# 51-2001-01-15_04_Power_Module_Schematic.net
KiCad netlist of a schematic drawn in Altium Designer
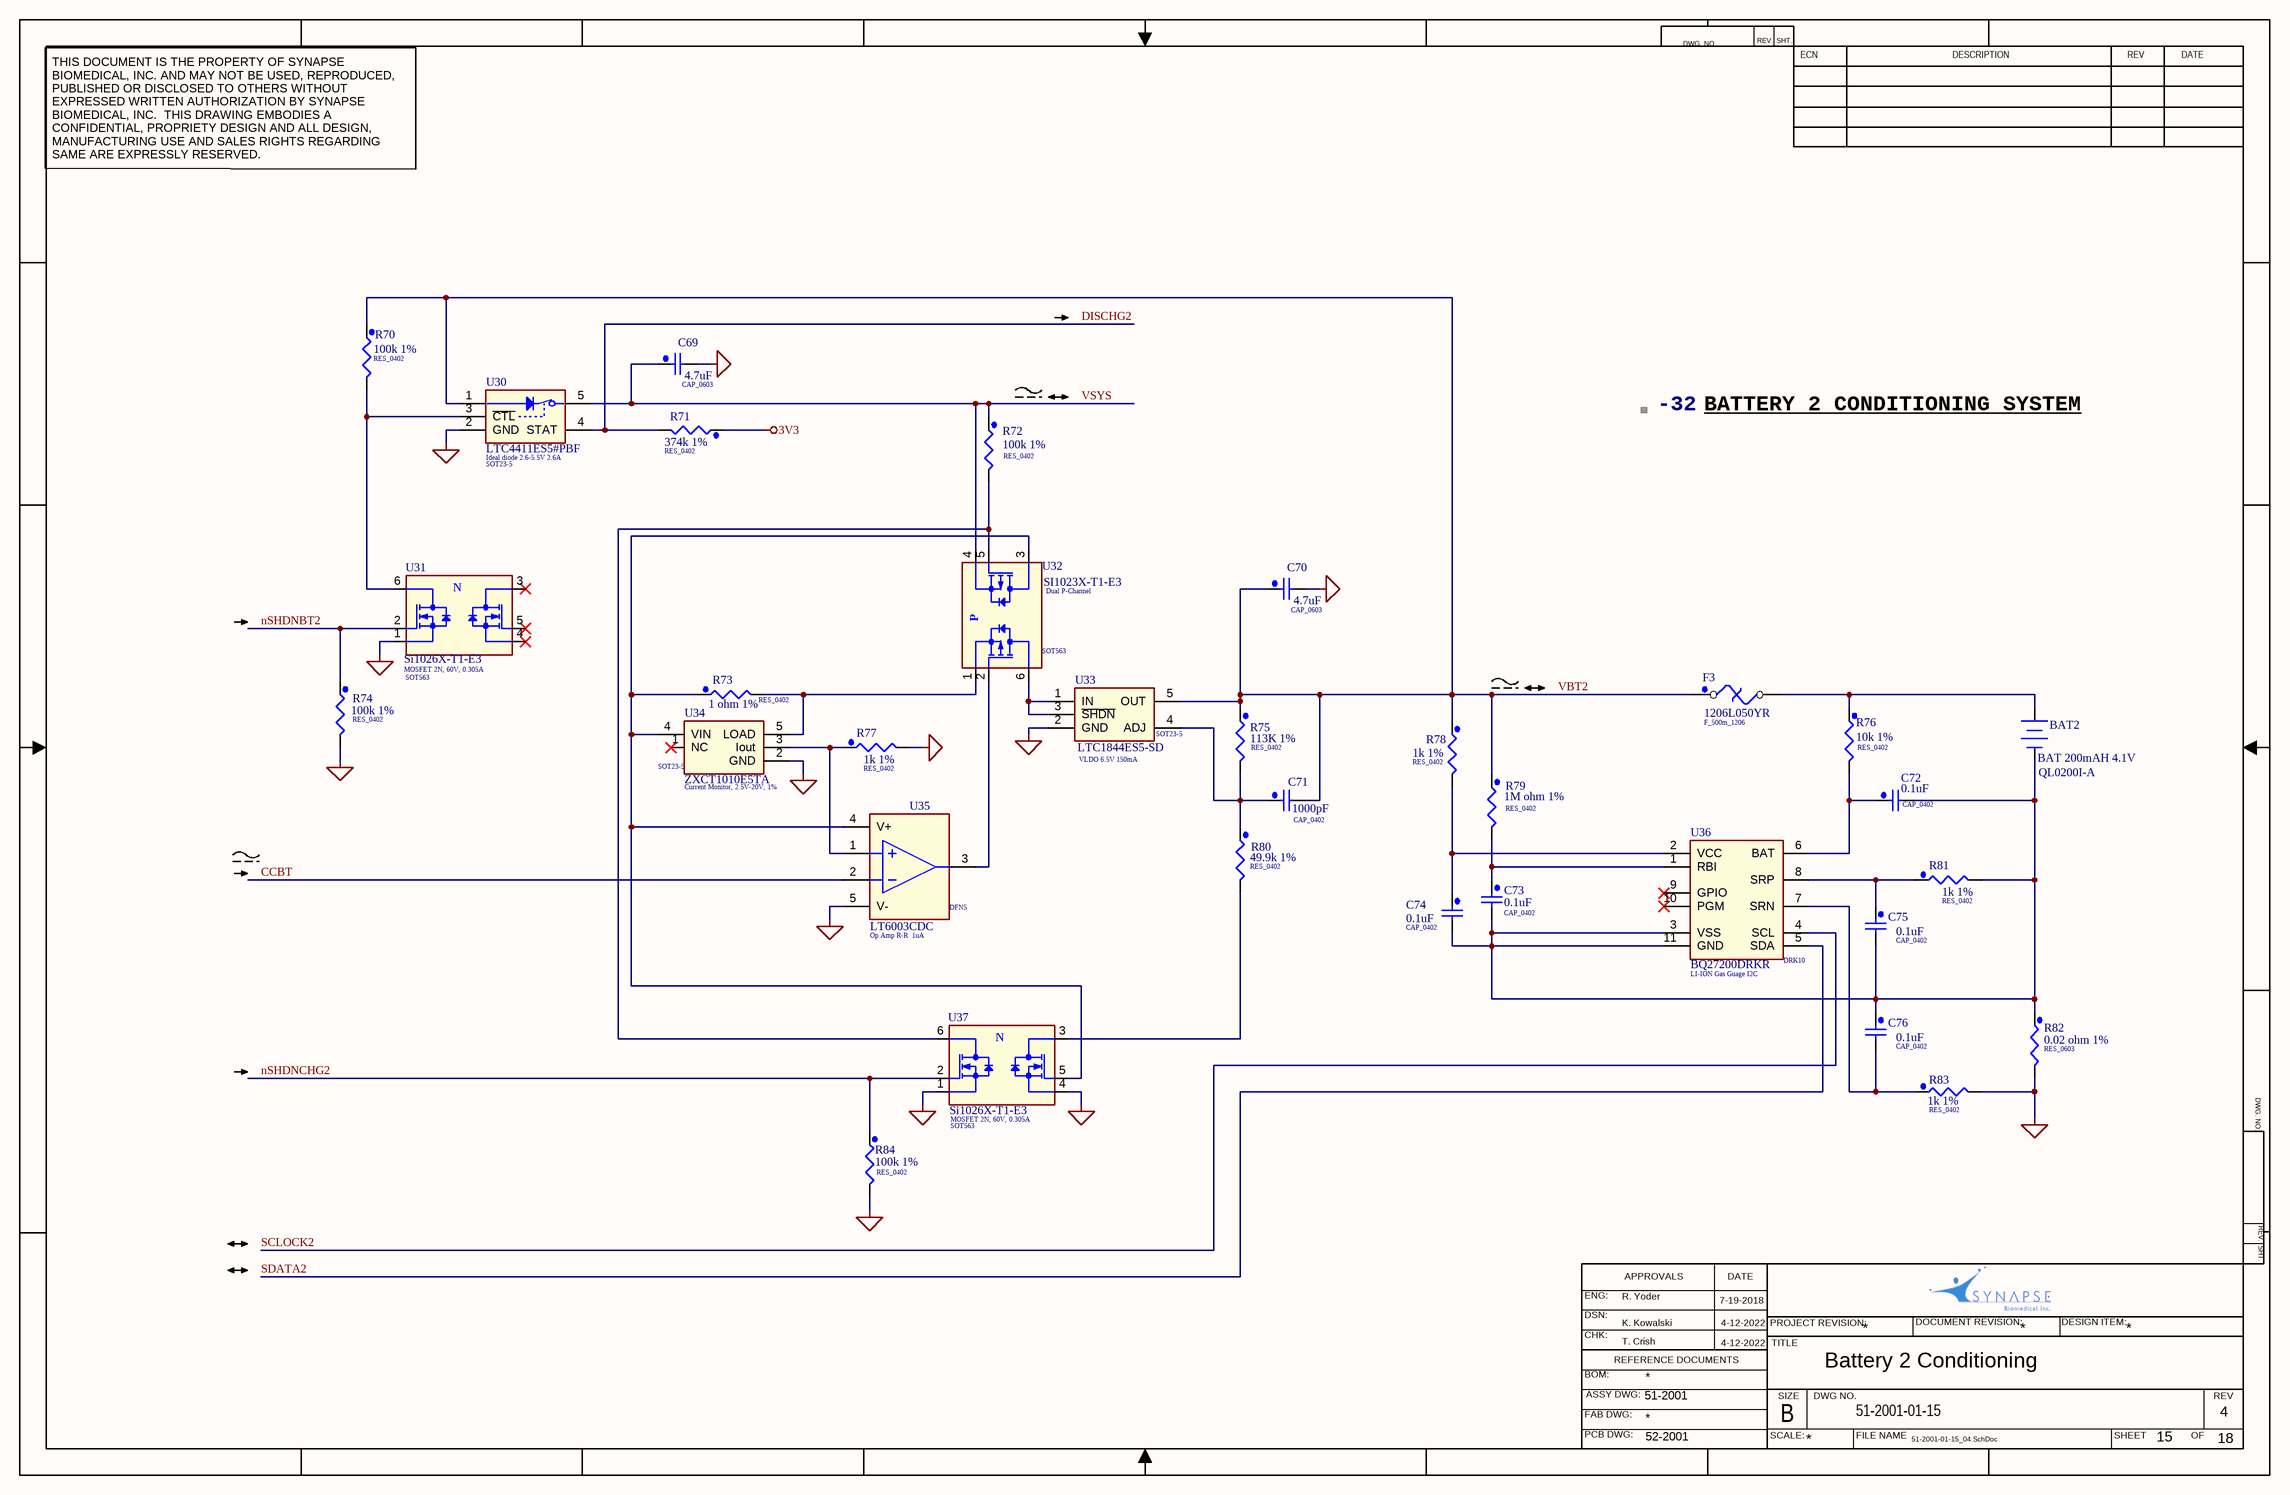
[diagram p0: 51-2001-01-15_04 Power Module Schematic.SchDoc]

(export (version "E")
  (design (tool "Eeschema 10.0.6"))
  (components
    (comp (ref "-32")
      (value "BOM_S1")
      (description "BOM item small graphic")
      (fields (field (name "XDESCRIPTION") "BATTERY 2 CONDITIONING SYSTEM"))
      (libsource (lib "BOM_sym") (part "BOM_S1"))
    )
    (comp (ref "BAT2")
      (value "BAT 200mAH 4.1V")
      (footprint "QL0200I-A")
      (description "Li-ion battery 200mAH 4.1V")
      (fields (field (name "MFR") "Quallion") (field (name "MPN") "QL0200I-A"))
      (libsource (lib "NNPS Integrated Parts") (part "QL0200I-A"))
    )
    (comp (ref "C69")
      (value "4.7uF")
      (footprint "CAP_0603")
      (description "4.7uF, 10V, X5R, 10%, 0603, RoHS")
      (fields
        (field (name "MFR") "Murata Electronics North America")
        (field (name "PACKAGEDESCRIPTION") "CAP_0603")
        (field (name "MPN") "GRM185R61A475KE11D")
      )
      (libsource (lib "NNPS Integrated Parts") (part "LMK107BJ475KA-T"))
    )
    (comp (ref "C70")
      (value "4.7uF")
      (footprint "CAP_0603")
      (description "4.7uF, 10V, X5R, 10%, 0603, RoHS")
      (fields
        (field (name "MFR") "Murata Electronics North America")
        (field (name "PACKAGEDESCRIPTION") "CAP_0603")
        (field (name "MPN") "GRM185R61A475KE11D")
      )
      (libsource (lib "NNPS Integrated Parts") (part "LMK107BJ475KA-T"))
    )
    (comp (ref "C71")
      (value "1000pF")
      (footprint "CAP_0402")
      (description "1000pF, 50V, C0G, 5%, 0402, RoHS")
      (fields
        (field (name "MFR") "Murata")
        (field (name "PACKAGEDESCRIPTION") "CAP_0402")
        (field (name "MPN") "GRM1555C1H102JA01D")
      )
      (libsource (lib "NNPS Integrated Parts") (part "GRM1555C1H102JA01D"))
    )
    (comp (ref "C72")
      (value "0.1uF")
      (footprint "CAP_0402")
      (description "0.1uF, 16V, X7R, 0402, RoHS")
      (fields
        (field (name "MFR") "Murata")
        (field (name "PACKAGEDESCRIPTION") "CAP_0402")
        (field (name "MPN") "GRM155R71C104KA88D")
      )
      (libsource (lib "NNPS Integrated Parts") (part "GRM155R71C104KA88D"))
    )
    (comp (ref "C73")
      (value "0.1uF")
      (footprint "CAP_0402")
      (description "0.1uF, 16V, X7R, 0402, RoHS")
      (fields
        (field (name "MFR") "Murata")
        (field (name "PACKAGEDESCRIPTION") "CAP_0402")
        (field (name "MPN") "GRM155R71C104KA88D")
      )
      (libsource (lib "NNPS Integrated Parts") (part "GRM155R71C104KA88D"))
    )
    (comp (ref "C74")
      (value "0.1uF")
      (footprint "CAP_0402")
      (description "0.1uF, 16V, X7R, 0402, RoHS")
      (fields
        (field (name "MFR") "Murata")
        (field (name "PACKAGEDESCRIPTION") "CAP_0402")
        (field (name "MPN") "GRM155R71C104KA88D")
      )
      (libsource (lib "NNPS Integrated Parts") (part "GRM155R71C104KA88D"))
    )
    (comp (ref "C75")
      (value "0.1uF")
      (footprint "CAP_0402")
      (description "0.1uF, 16V, X7R, 0402, RoHS")
      (fields
        (field (name "MFR") "Murata")
        (field (name "PACKAGEDESCRIPTION") "CAP_0402")
        (field (name "MPN") "GRM155R71C104KA88D")
      )
      (libsource (lib "NNPS Integrated Parts") (part "GRM155R71C104KA88D"))
    )
    (comp (ref "C76")
      (value "0.1uF")
      (footprint "CAP_0402")
      (description "0.1uF, 16V, X7R, 0402, RoHS")
      (fields
        (field (name "MFR") "Murata")
        (field (name "PACKAGEDESCRIPTION") "CAP_0402")
        (field (name "MPN") "GRM155R71C104KA88D")
      )
      (libsource (lib "NNPS Integrated Parts") (part "GRM155R71C104KA88D"))
    )
    (comp (ref "F3")
      (value "F_500m_1206")
      (footprint "FUSE_1206")
      (description "PTC Resettable, 500mA, 0.4 ohm,  6V, 1206, RoHS")
      (fields
        (field (name "MFR") "Littelfuse")
        (field (name "PACKAGEDESCRIPTION") "F_500m_1206")
        (field (name "MPN") "1206L050YR")
      )
      (libsource (lib "NNPS Integrated Parts") (part "1206L050YR"))
    )
    (comp (ref "R70")
      (value "100k 1%")
      (footprint "RES_0402")
      (description "100k ohm, 1%, 1/16W, smd, 0402, RoHS")
      (fields
        (field (name "MFR") "Vishay Dale")
        (field (name "PACKAGEDESCRIPTION") "RES_0402")
        (field (name "MPN") "CRCW0402100KFKED")
      )
      (libsource (lib "NNPS Integrated Parts") (part "MCR01MZPF1003"))
    )
    (comp (ref "R71")
      (value "374k 1%")
      (footprint "RES_0402")
      (description "374k ohm, 1%, 1/16W, 0402,RoHS")
      (fields
        (field (name "MFR") "Vishay Dale")
        (field (name "PACKAGEDESCRIPTION") "RES_0402")
        (field (name "MPN") "CRCW0402374KFKED")
      )
      (libsource (lib "NNPS Integrated Parts") (part "CRCW0402374KFKED"))
    )
    (comp (ref "R72")
      (value "100k 1%")
      (footprint "RES_0402")
      (description "100k ohm, 1%, 1/16W, smd, 0402, RoHS")
      (fields
        (field (name "MFR") "Vishay Dale")
        (field (name "PACKAGEDESCRIPTION") "RES_0402")
        (field (name "MPN") "CRCW0402100KFKED")
      )
      (libsource (lib "NNPS Integrated Parts") (part "MCR01MZPF1003"))
    )
    (comp (ref "R73")
      (value "1 ohm 1%")
      (footprint "RES_0402")
      (description "1.0 ohm, 1%, 1/16W, 0402, RoHS")
      (fields
        (field (name "MFR") "Vishay")
        (field (name "PACKAGEDESCRIPTION") "RES_0402")
        (field (name "MPN") "CRCW04021R00FNED")
      )
      (libsource (lib "NNPS Integrated Parts") (part "CRCW04021R00FNED"))
    )
    (comp (ref "R74")
      (value "100k 1%")
      (footprint "RES_0402")
      (description "100k ohm, 1%, 1/16W, smd, 0402, RoHS")
      (fields
        (field (name "MFR") "Vishay Dale")
        (field (name "PACKAGEDESCRIPTION") "RES_0402")
        (field (name "MPN") "CRCW0402100KFKED")
      )
      (libsource (lib "NNPS Integrated Parts") (part "MCR01MZPF1003"))
    )
    (comp (ref "R75")
      (value "113K 1%")
      (footprint "RES_0402")
      (description "113k ohm, 1%, 1/16W, 0402, RoHS")
      (fields
        (field (name "MFR") "Vishay Dale")
        (field (name "PACKAGEDESCRIPTION") "RES_0402")
        (field (name "MPN") "CRCW0402113KFKED")
      )
      (libsource (lib "NNPS Integrated Parts") (part "ERJ-2RKF1133X"))
    )
    (comp (ref "R76")
      (value "10k 1%")
      (footprint "RES_0402")
      (description "10.0k ohm, 1%, 1/16W, smd, 0402, RoHS")
      (fields
        (field (name "MFR") "Vishay Dale")
        (field (name "PACKAGEDESCRIPTION") "RES_0402")
        (field (name "MPN") "CRCW040210K0FKED")
      )
      (libsource (lib "NNPS Integrated Parts") (part "MCR01MZPF1002"))
    )
    (comp (ref "R77")
      (value "1k 1%")
      (footprint "RES_0402")
      (description "1.0k ohm 1% 1/16W smd 0402 RoHS")
      (fields
        (field (name "MFR") "Vishay Dale")
        (field (name "PACKAGEDESCRIPTION") "RES_0402")
        (field (name "MPN") "CRCW04021K00FKED")
      )
      (libsource (lib "NNPS Integrated Parts") (part "MCR01MZPF1001"))
    )
    (comp (ref "R78")
      (value "1k 1%")
      (footprint "RES_0402")
      (description "1.0k ohm 1% 1/16W smd 0402 RoHS")
      (fields
        (field (name "MFR") "Vishay Dale")
        (field (name "PACKAGEDESCRIPTION") "RES_0402")
        (field (name "MPN") "CRCW04021K00FKED")
      )
      (libsource (lib "NNPS Integrated Parts") (part "MCR01MZPF1001"))
    )
    (comp (ref "R79")
      (value "1M ohm 1%")
      (footprint "RES_0402")
      (description "1M ohm, 1/16W, 1%, 0402, RoHS")
      (fields
        (field (name "MFR") "Vishay Dale")
        (field (name "PACKAGEDESCRIPTION") "RES_0402")
        (field (name "MPN") "CRCW04021M00FKED")
      )
      (libsource (lib "NNPS Integrated Parts") (part "MCR01MZPF1004"))
    )
    (comp (ref "R80")
      (value "49.9k 1%")
      (footprint "RES_0402")
      (description "49.9k ohm, 1%, 1/16W, 0402, RoHS")
      (fields
        (field (name "MFR") "Vishay Dale")
        (field (name "PACKAGEDESCRIPTION") "RES_0402")
        (field (name "MPN") "CRCW040249K9FKED")
      )
      (libsource (lib "NNPS Integrated Parts") (part "MCR01MZPF4992"))
    )
    (comp (ref "R81")
      (value "1k 1%")
      (footprint "RES_0402")
      (description "1.0k ohm 1% 1/16W smd 0402 RoHS")
      (fields
        (field (name "MFR") "Vishay Dale")
        (field (name "PACKAGEDESCRIPTION") "RES_0402")
        (field (name "MPN") "CRCW04021K00FKED")
      )
      (libsource (lib "NNPS Integrated Parts") (part "MCR01MZPF1001"))
    )
    (comp (ref "R82")
      (value "0.02 ohm 1%")
      (footprint "RES_0603")
      (description "0.02 ohm, 1%, 1/10W, 0603, RoHS")
      (fields
        (field (name "MFR") "Vishay Dale")
        (field (name "PACKAGEDESCRIPTION") "RES_0603")
        (field (name "MPN") "WSL0603R0200FEA")
      )
      (libsource (lib "NNPS Integrated Parts") (part "WSL0603R0200FEA"))
    )
    (comp (ref "R83")
      (value "1k 1%")
      (footprint "RES_0402")
      (description "1.0k ohm 1% 1/16W smd 0402 RoHS")
      (fields
        (field (name "MFR") "Vishay Dale")
        (field (name "PACKAGEDESCRIPTION") "RES_0402")
        (field (name "MPN") "CRCW04021K00FKED")
      )
      (libsource (lib "NNPS Integrated Parts") (part "MCR01MZPF1001"))
    )
    (comp (ref "R84")
      (value "100k 1%")
      (footprint "RES_0402")
      (description "100k ohm, 1%, 1/16W, smd, 0402, RoHS")
      (fields
        (field (name "MFR") "Vishay Dale")
        (field (name "PACKAGEDESCRIPTION") "RES_0402")
        (field (name "MPN") "CRCW0402100KFKED")
      )
      (libsource (lib "NNPS Integrated Parts") (part "MCR01MZPF1003"))
    )
    (comp (ref "U30")
      (value "Ideal diode 2.6-5.5V 2.6A")
      (footprint "SOT23-5")
      (description "Ideal diode, 2.6-5.5V, 2.6A, SOT23-5, RoHS")
      (fields
        (field (name "MFR") "Linear Technology")
        (field (name "PACKAGEDESCRIPTION") "SOT23-5")
        (field (name "MPN") "LTC4411ES5#PBF")
      )
      (libsource (lib "NNPS Integrated Parts") (part "LTC4411ES5"))
    )
    (comp (ref "U31")
      (value "MOSFET 2N, 60V, 0.305A")
      (footprint "SOT-563")
      (description "MOSFET 2N, 60V, 0.305A, RoHS")
      (fields
        (field (name "MFR") "Vishay Siliconix")
        (field (name "PACKAGEDESCRIPTION") "SOT563")
        (field (name "MPN") "Si1026X-T1-E3")
      )
      (libsource (lib "NNPS Integrated Parts") (part "Si1026X-T1-E3"))
    )
    (comp (ref "U32")
      (value "Dual P-Channel")
      (footprint "SOT-563")
      (description "Dual P-Channel Mosfet, SOT563, RoHS")
      (fields
        (field (name "MFR") "Vishay Siliconix")
        (field (name "PACKAGEDESCRIPTION") "SOT563")
        (field (name "MPN") "SI1023X-T1-E3")
      )
      (libsource (lib "NNPS Integrated Parts") (part "SI1023X-T1-E3"))
    )
    (comp (ref "U33")
      (value "VLDO 6.5V 150mA")
      (footprint "SOT23-5")
      (description "VLDO, 150mA, SOT23-5, RoHS")
      (fields
        (field (name "MFR") "Linear Technology")
        (field (name "PACKAGEDESCRIPTION") "SOT23-5")
        (field (name "MPN") "LTC1844ES5-SD")
      )
      (libsource (lib "NNPS Integrated Parts") (part "LTC1844ES5-SD"))
    )
    (comp (ref "U34")
      (value "Current Monitor, 2.5V-20V, 1%")
      (footprint "SOT23-5")
      (description "Current Monitor, 2.5V-20V, 1%, RoHS")
      (fields
        (field (name "MFR") "Diodes Incorporated")
        (field (name "PACKAGEDESCRIPTION") "SOT23-5")
        (field (name "MPN") "ZXCT1010E5TA")
      )
      (libsource (lib "NNPS Integrated Parts") (part "ZXCT1010E5TA"))
    )
    (comp (ref "U35")
      (value "Op Amp R-R  1uA")
      (footprint "DFN4")
      (description "Op Amp, R-R, 1uA, RoHS")
      (fields
        (field (name "PACKAGEDESCRIPTION") "DFN5")
        (field (name "MFR") "Linear Technology")
        (field (name "MPN") "LT6003CDC")
      )
      (libsource (lib "NNPS Integrated Parts") (part "LT6003CDC"))
    )
    (comp (ref "U36")
      (value "LI-ION Gas Guage I2C")
      (footprint "QFN10")
      (description "LI-ION Gas Guage, I2C, QFN10, RoHS")
      (fields
        (field (name "MFR") "Texas Instruments")
        (field (name "PACKAGEDESCRIPTION") "DRK10")
        (field (name "MPN") "BQ27200DRKR")
      )
      (libsource (lib "NNPS Integrated Parts") (part "BQ27200DRKR"))
    )
    (comp (ref "U37")
      (value "MOSFET 2N, 60V, 0.305A")
      (footprint "SOT-563")
      (description "MOSFET 2N, 60V, 0.305A, RoHS")
      (fields
        (field (name "MFR") "Vishay Siliconix")
        (field (name "PACKAGEDESCRIPTION") "SOT563")
        (field (name "MPN") "Si1026X-T1-E3")
      )
      (libsource (lib "NNPS Integrated Parts") (part "Si1026X-T1-E3"))
    )
  )
  (nets
    (net (code "1") (name "/CCBT") (class "Default")
      (node (ref "U35") (pin "2") (pinfunction "-IN_2") (pintype "passive"))
    )
    (net (code "2") (name "/DISCHG2") (class "Default")
      (node (ref "R71") (pin "2") (pinfunction "2_2") (pintype "passive"))
      (node (ref "U30") (pin "4") (pinfunction "STAT_4") (pintype "passive"))
    )
    (net (code "3") (name "/SCLOCK2") (class "Default")
      (node (ref "U36") (pin "4") (pinfunction "SCL_4") (pintype "passive"))
    )
    (net (code "4") (name "/SDATA2") (class "Default")
      (node (ref "U36") (pin "5") (pinfunction "SDA_5") (pintype "passive"))
    )
    (net (code "5") (name "/VBT2") (class "Default")
      (node (ref "C70") (pin "1") (pinfunction "1_1") (pintype "passive"))
      (node (ref "C71") (pin "2") (pinfunction "2_2") (pintype "passive"))
      (node (ref "F3") (pin "1") (pinfunction "1_1") (pintype "passive"))
      (node (ref "R70") (pin "1") (pinfunction "1_1") (pintype "passive"))
      (node (ref "R75") (pin "1") (pinfunction "1_1") (pintype "passive"))
      (node (ref "R78") (pin "1") (pinfunction "1_1") (pintype "passive"))
      (node (ref "R79") (pin "1") (pinfunction "1_1") (pintype "passive"))
      (node (ref "U30") (pin "1") (pinfunction "IN_1") (pintype "passive"))
      (node (ref "U33") (pin "5") (pinfunction "OUT_5") (pintype "passive"))
    )
    (net (code "6") (name "/VSYS") (class "Default")
      (node (ref "C69") (pin "1") (pinfunction "1_1") (pintype "passive"))
      (node (ref "R72") (pin "1") (pinfunction "1_1") (pintype "passive"))
      (node (ref "U30") (pin "5") (pinfunction "OUT_5") (pintype "passive"))
      (node (ref "U32") (pin "4") (pinfunction "S2_4") (pintype "passive"))
    )
    (net (code "7") (name "/nSHDNBT2") (class "Default")
      (node (ref "R74") (pin "1") (pinfunction "1_1") (pintype "passive"))
      (node (ref "U31") (pin "2") (pinfunction "G1_2") (pintype "passive"))
    )
    (net (code "8") (name "/nSHDNCHG2") (class "Default")
      (node (ref "R84") (pin "1") (pinfunction "1_1") (pintype "passive"))
      (node (ref "U37") (pin "2") (pinfunction "G1_2") (pintype "passive"))
    )
    (net (code "9") (name "3V3") (class "Default")
      (node (ref "R71") (pin "1") (pinfunction "1_1") (pintype "passive"))
    )
    (net (code "10") (name "<NO NET>") (class "Default")
      (node (ref "R84") (pin "2") (pinfunction "2_2") (pintype "passive"))
    )
    (net (code "11") (name "GND") (class "Default")
      (node (ref "C69") (pin "2") (pinfunction "2_2") (pintype "passive"))
      (node (ref "C70") (pin "2") (pinfunction "2_2") (pintype "passive"))
      (node (ref "R74") (pin "2") (pinfunction "2_2") (pintype "passive"))
      (node (ref "R77") (pin "2") (pinfunction "2_2") (pintype "passive"))
      (node (ref "R82") (pin "2") (pinfunction "2_2") (pintype "passive"))
      (node (ref "R83") (pin "2") (pinfunction "2_2") (pintype "passive"))
      (node (ref "U30") (pin "2") (pinfunction "GND_2") (pintype "passive"))
      (node (ref "U31") (pin "1") (pinfunction "S1_1") (pintype "passive"))
      (node (ref "U33") (pin "2") (pinfunction "GND_2") (pintype "passive"))
      (node (ref "U34") (pin "2") (pinfunction "GND_2") (pintype "power_in"))
      (node (ref "U35") (pin "5") (pinfunction "V-_5") (pintype "power_in"))
      (node (ref "U37") (pin "1") (pinfunction "S1_1") (pintype "passive"))
      (node (ref "U37") (pin "4") (pinfunction "S2_4") (pintype "passive"))
    )
    (net (code "12") (name "Net-(BAT2-+)") (class "Default")
      (node (ref "BAT2") (pin "1") (pinfunction "+_1") (pintype "passive"))
      (node (ref "F3") (pin "2") (pinfunction "2_2") (pintype "passive"))
      (node (ref "R76") (pin "1") (pinfunction "1_1") (pintype "passive"))
    )
    (net (code "13") (name "Net-(BAT2--)") (class "Default")
      (node (ref "BAT2") (pin "2") (pinfunction "-_2") (pintype "passive"))
      (node (ref "C72") (pin "2") (pinfunction "2_2") (pintype "passive"))
      (node (ref "C73") (pin "2") (pinfunction "2_2") (pintype "passive"))
      (node (ref "C74") (pin "2") (pinfunction "2_2") (pintype "passive"))
      (node (ref "C75") (pin "2") (pinfunction "2_2") (pintype "passive"))
      (node (ref "C76") (pin "1") (pinfunction "1_1") (pintype "passive"))
      (node (ref "R81") (pin "2") (pinfunction "2_2") (pintype "passive"))
      (node (ref "R82") (pin "1") (pinfunction "1_1") (pintype "passive"))
      (node (ref "U36") (pin "11") (pinfunction "GND_11") (pintype "passive"))
      (node (ref "U36") (pin "3") (pinfunction "VSS_3") (pintype "passive"))
    )
    (net (code "14") (name "Net-(U30-~{CTL})") (class "Default")
      (node (ref "R70") (pin "2") (pinfunction "2_2") (pintype "passive"))
      (node (ref "U30") (pin "3") (pinfunction "~{CTL}_3") (pintype "passive"))
      (node (ref "U31") (pin "6") (pinfunction "D1_6") (pintype "passive"))
    )
    (net (code "15") (name "Net-(U32-D1)") (class "Default")
      (node (ref "U32") (pin "6") (pinfunction "D1_6") (pintype "passive"))
      (node (ref "U33") (pin "1") (pinfunction "IN_1") (pintype "passive"))
      (node (ref "U33") (pin "3") (pinfunction "SHDN_3") (pintype "passive"))
    )
    (net (code "16") (name "Net-(U32-D2)") (class "Default")
      (node (ref "R73") (pin "1") (pinfunction "1_1") (pintype "passive"))
      (node (ref "U32") (pin "3") (pinfunction "D2_3") (pintype "passive"))
      (node (ref "U34") (pin "4") (pinfunction "VIN_4") (pintype "power_in"))
      (node (ref "U35") (pin "4") (pinfunction "V+_4") (pintype "power_in"))
      (node (ref "U37") (pin "5") (pinfunction "G2_5") (pintype "passive"))
    )
    (net (code "17") (name "Net-(U32-G1)") (class "Default")
      (node (ref "U32") (pin "2") (pinfunction "G1_2") (pintype "passive"))
      (node (ref "U35") (pin "3") (pinfunction "OUT_A_3") (pintype "passive"))
    )
    (net (code "18") (name "Net-(U32-G2)") (class "Default")
      (node (ref "R72") (pin "2") (pinfunction "2_2") (pintype "passive"))
      (node (ref "U32") (pin "5") (pinfunction "G2_5") (pintype "passive"))
      (node (ref "U37") (pin "6") (pinfunction "D1_6") (pintype "passive"))
    )
    (net (code "19") (name "Net-(U32-S1)") (class "Default")
      (node (ref "R73") (pin "2") (pinfunction "2_2") (pintype "passive"))
      (node (ref "U32") (pin "1") (pinfunction "S1_1") (pintype "passive"))
      (node (ref "U34") (pin "5") (pinfunction "LOAD_5") (pintype "passive"))
    )
    (net (code "20") (name "Net-(U33-ADJ)") (class "Default")
      (node (ref "C71") (pin "1") (pinfunction "1_1") (pintype "passive"))
      (node (ref "R75") (pin "2") (pinfunction "2_2") (pintype "passive"))
      (node (ref "R80") (pin "1") (pinfunction "1_1") (pintype "passive"))
      (node (ref "U33") (pin "4") (pinfunction "ADJ_4") (pintype "passive"))
    )
    (net (code "21") (name "Net-(U34-Iout)") (class "Default")
      (node (ref "R77") (pin "1") (pinfunction "1_1") (pintype "passive"))
      (node (ref "U34") (pin "3") (pinfunction "Iout_3") (pintype "passive"))
      (node (ref "U35") (pin "1") (pinfunction "+IN_1") (pintype "passive"))
    )
    (net (code "22") (name "Net-(U36-BAT)") (class "Default")
      (node (ref "C72") (pin "1") (pinfunction "1_1") (pintype "passive"))
      (node (ref "R76") (pin "2") (pinfunction "2_2") (pintype "passive"))
      (node (ref "U36") (pin "6") (pinfunction "BAT_6") (pintype "passive"))
    )
    (net (code "23") (name "Net-(U36-RBI)") (class "Default")
      (node (ref "C73") (pin "1") (pinfunction "1_1") (pintype "passive"))
      (node (ref "R79") (pin "2") (pinfunction "2_2") (pintype "passive"))
      (node (ref "U36") (pin "1") (pinfunction "RBI_1") (pintype "passive"))
    )
    (net (code "24") (name "Net-(U36-SRN)") (class "Default")
      (node (ref "C76") (pin "2") (pinfunction "2_2") (pintype "passive"))
      (node (ref "R83") (pin "1") (pinfunction "1_1") (pintype "passive"))
      (node (ref "U36") (pin "7") (pinfunction "SRN_7") (pintype "passive"))
    )
    (net (code "25") (name "Net-(U36-SRP)") (class "Default")
      (node (ref "C75") (pin "1") (pinfunction "1_1") (pintype "passive"))
      (node (ref "R81") (pin "1") (pinfunction "1_1") (pintype "passive"))
      (node (ref "U36") (pin "8") (pinfunction "SRP_8") (pintype "passive"))
    )
    (net (code "26") (name "Net-(U36-VCC)") (class "Default")
      (node (ref "C74") (pin "1") (pinfunction "1_1") (pintype "passive"))
      (node (ref "R78") (pin "2") (pinfunction "2_2") (pintype "passive"))
      (node (ref "U36") (pin "2") (pinfunction "VCC_2") (pintype "passive"))
    )
    (net (code "27") (name "Net-(U37-D2)") (class "Default")
      (node (ref "R80") (pin "2") (pinfunction "2_2") (pintype "passive"))
      (node (ref "U37") (pin "3") (pinfunction "D2_3") (pintype "passive"))
    )
    (net (code "28") (name "unconnected-(U31-D2-Pad3)") (class "Default")
      (node (ref "U31") (pin "3") (pinfunction "D2_3") (pintype "passive+no_connect"))
    )
    (net (code "29") (name "unconnected-(U31-G2-Pad5)") (class "Default")
      (node (ref "U31") (pin "5") (pinfunction "G2_5") (pintype "passive+no_connect"))
    )
    (net (code "30") (name "unconnected-(U31-S2-Pad4)") (class "Default")
      (node (ref "U31") (pin "4") (pinfunction "S2_4") (pintype "passive+no_connect"))
    )
    (net (code "31") (name "unconnected-(U34-NC-Pad1)") (class "Default")
      (node (ref "U34") (pin "1") (pinfunction "NC_1") (pintype "tri_state+no_connect"))
    )
    (net (code "32") (name "unconnected-(U36-GPIO-Pad9)") (class "Default")
      (node (ref "U36") (pin "9") (pinfunction "GPIO_9") (pintype "passive+no_connect"))
    )
    (net (code "33") (name "unconnected-(U36-PGM-Pad10)") (class "Default")
      (node (ref "U36") (pin "10") (pinfunction "PGM_10") (pintype "passive+no_connect"))
    )
  )
)
